# CM0_Controller_STM32F030C6T6.net
KiCad netlist of a schematic drawn in Altium Designer
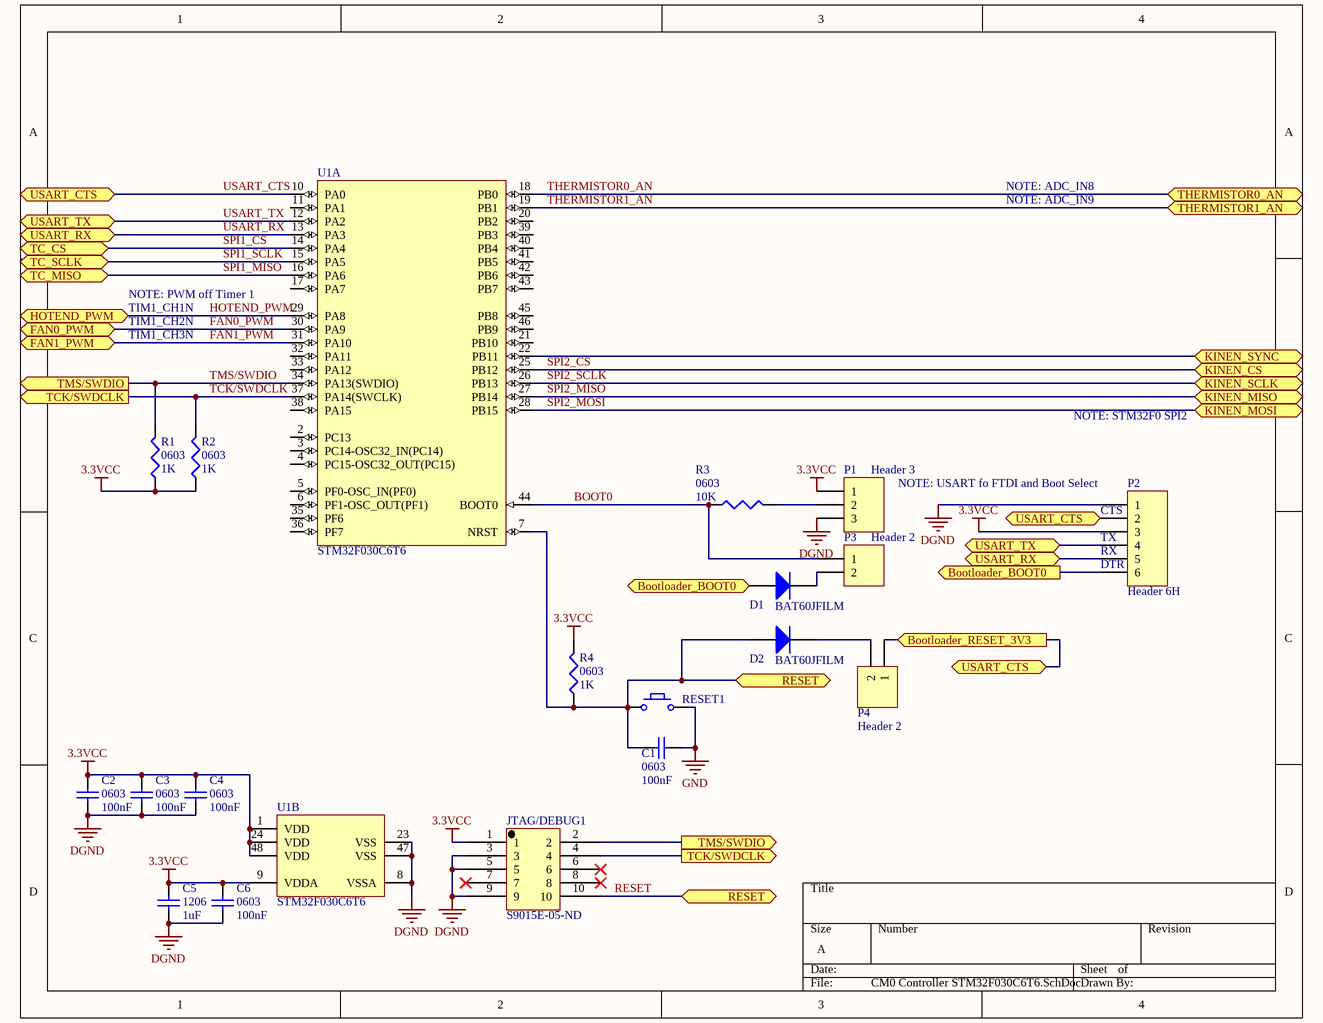
[diagram p0: CM0 Controller STM32F030C6T6.SchDoc]

(export (version "E")
  (design (tool "Eeschema 10.0.6"))
  (components
    (comp (ref "C1")
      (value "0603")
      (footprint "1608[0603]")
      (description "Capacitor (Semiconductor SIM Model)")
      (fields (field (name "ALTIUM_VALUE") "100nF") (field (name "PUBLISHER") "Altium Limited"))
      (libsource (lib "Miscellaneous Devices") (part "Cap Semi"))
    )
    (comp (ref "C2")
      (value "0603")
      (footprint "1608[0603]")
      (description "Capacitor (Semiconductor SIM Model)")
      (fields (field (name "ALTIUM_VALUE") "100nF") (field (name "PUBLISHER") "Altium Limited"))
      (libsource (lib "Miscellaneous Devices") (part "Cap Semi"))
    )
    (comp (ref "C3")
      (value "0603")
      (footprint "1608[0603]")
      (description "Capacitor (Semiconductor SIM Model)")
      (fields (field (name "ALTIUM_VALUE") "100nF") (field (name "PUBLISHER") "Altium Limited"))
      (libsource (lib "Miscellaneous Devices") (part "Cap Semi"))
    )
    (comp (ref "C4")
      (value "0603")
      (footprint "1608[0603]")
      (description "Capacitor (Semiconductor SIM Model)")
      (fields (field (name "ALTIUM_VALUE") "100nF") (field (name "PUBLISHER") "Altium Limited"))
      (libsource (lib "Miscellaneous Devices") (part "Cap Semi"))
    )
    (comp (ref "C5")
      (value "1206")
      (footprint "C1206")
      (description "Capacitor (Semiconductor SIM Model)")
      (fields (field (name "ALTIUM_VALUE") "1uF") (field (name "PUBLISHER") "Altium Limited"))
      (libsource (lib "Miscellaneous Devices") (part "Cap Semi"))
    )
    (comp (ref "C6")
      (value "0603")
      (footprint "1608[0603]")
      (description "Capacitor (Semiconductor SIM Model)")
      (fields (field (name "ALTIUM_VALUE") "100nF") (field (name "PUBLISHER") "Altium Limited"))
      (libsource (lib "Miscellaneous Devices") (part "Cap Semi"))
    )
    (comp (ref "D1")
      (value "BAT60JFILM")
      (footprint "SOD-323")
      (description "Default Diode")
      (fields (field (name "PUBLISHER") "Altium Limited"))
      (libsource (lib "Miscellaneous Devices") (part "Diode"))
    )
    (comp (ref "D2")
      (value "BAT60JFILM")
      (footprint "SOD-323")
      (description "Default Diode")
      (fields (field (name "PUBLISHER") "Altium Limited"))
      (libsource (lib "Miscellaneous Devices") (part "Diode"))
    )
    (comp (ref "JTAG/DEBUG1")
      (value "S9015E-05-ND")
      (footprint "S9015E-05-ND")
      (libsource (lib "Adams Altium Library") (part "S9015E-05-ND"))
    )
    (comp (ref "P1")
      (value "Header 3")
      (footprint "HDR1X3")
      (description "Header, 3-Pin")
      (fields (field (name "PUBLISHER") "Altium Limited"))
      (libsource (lib "Miscellaneous Connectors") (part "Header 3"))
    )
    (comp (ref "P2")
      (value "Header 6H")
      (footprint "HDR1X6H")
      (description "Header, 6-Pin, Right Angle")
      (fields (field (name "PUBLISHER") "Altium Limited"))
      (libsource (lib "Miscellaneous Connectors") (part "Header 6H"))
    )
    (comp (ref "P3")
      (value "Header 2")
      (footprint "HDR1X2")
      (description "Header, 2-Pin")
      (fields (field (name "PUBLISHER") "Altium Limited"))
      (libsource (lib "Miscellaneous Connectors") (part "Header 2"))
    )
    (comp (ref "P4")
      (value "Header 2")
      (footprint "HDR1X2")
      (description "Header, 2-Pin")
      (fields (field (name "PUBLISHER") "Altium Limited"))
      (libsource (lib "") (part "Header 2_1"))
    )
    (comp (ref "R1")
      (value "0603")
      (footprint "J1-0603")
      (description "Resistor")
      (fields (field (name "ALTIUM_VALUE") "1K") (field (name "PUBLISHER") "Altium Limited"))
      (libsource (lib "Miscellaneous Devices") (part "Res3"))
    )
    (comp (ref "R2")
      (value "0603")
      (footprint "J1-0603")
      (description "Resistor")
      (fields (field (name "ALTIUM_VALUE") "1K") (field (name "PUBLISHER") "Altium Limited"))
      (libsource (lib "Miscellaneous Devices") (part "Res3"))
    )
    (comp (ref "R3")
      (value "0603")
      (footprint "J1-0603")
      (description "Resistor")
      (fields (field (name "ALTIUM_VALUE") "10K") (field (name "PUBLISHER") "Altium Limited"))
      (libsource (lib "Miscellaneous Devices") (part "Res3"))
    )
    (comp (ref "R4")
      (value "0603")
      (footprint "J1-0603")
      (description "Resistor")
      (fields (field (name "ALTIUM_VALUE") "1K") (field (name "PUBLISHER") "Altium Limited"))
      (libsource (lib "Miscellaneous Devices") (part "Res3"))
    )
    (comp (ref "RESET1")
      (value "Tactile Switch")
      (footprint "tactile switch")
      (libsource (lib "Adams Altium Library") (part "Tactile Switch"))
    )
    (comp (ref "U1")
      (value "STM32F030C6T6")
      (footprint "STM-LQFP48_L")
      (libsource (lib "STMicroelectronics STM32 F0") (part "STM32F030C6T6"))
    )
  )
  (nets
    (net (code "1") (name "/BOOT0") (class "Default")
      (node (ref "P3") (pin "1") (pinfunction "1_1") (pintype "passive"))
      (node (ref "R3") (pin "1") (pinfunction "1_1") (pintype "passive"))
      (node (ref "U1") (pin "44") (pinfunction "BOOT0_44") (pintype "input"))
    )
    (net (code "2") (name "/Bootloader_BOOT0") (class "Default")
      (node (ref "D1") (pin "1") (pinfunction "A_1") (pintype "passive"))
      (node (ref "P2") (pin "6") (pinfunction "6_6") (pintype "passive"))
    )
    (net (code "3") (name "/FAN0_PWM") (class "Default")
      (node (ref "U1") (pin "30") (pinfunction "PA9_30") (pintype "bidirectional"))
    )
    (net (code "4") (name "/FAN1_PWM") (class "Default")
      (node (ref "U1") (pin "31") (pinfunction "PA10_31") (pintype "bidirectional"))
    )
    (net (code "5") (name "/HOTEND_PWM") (class "Default")
      (node (ref "U1") (pin "29") (pinfunction "PA8_29") (pintype "bidirectional"))
    )
    (net (code "6") (name "/KINEN_SYNC") (class "Default")
      (node (ref "U1") (pin "22") (pinfunction "PB11_22") (pintype "bidirectional"))
    )
    (net (code "7") (name "/RESET") (class "Default")
      (node (ref "C1") (pin "2") (pinfunction "2_2") (pintype "passive"))
      (node (ref "D2") (pin "1") (pinfunction "A_1") (pintype "passive"))
      (node (ref "JTAG/DEBUG1") (pin "10") (pinfunction "10_10") (pintype "passive"))
      (node (ref "R4") (pin "1") (pinfunction "1_1") (pintype "passive"))
      (node (ref "RESET1") (pin "1") (pintype "passive"))
      (node (ref "U1") (pin "7") (pinfunction "NRST_7") (pintype "bidirectional"))
    )
    (net (code "8") (name "/SPI1_CS") (class "Default")
      (node (ref "U1") (pin "14") (pinfunction "PA4_14") (pintype "bidirectional"))
    )
    (net (code "9") (name "/SPI1_MISO") (class "Default")
      (node (ref "U1") (pin "16") (pinfunction "PA6_16") (pintype "bidirectional"))
    )
    (net (code "10") (name "/SPI1_SCLK") (class "Default")
      (node (ref "U1") (pin "15") (pinfunction "PA5_15") (pintype "bidirectional"))
    )
    (net (code "11") (name "/SPI2_CS") (class "Default")
      (node (ref "U1") (pin "25") (pinfunction "PB12_25") (pintype "bidirectional"))
    )
    (net (code "12") (name "/SPI2_MISO") (class "Default")
      (node (ref "U1") (pin "27") (pinfunction "PB14_27") (pintype "bidirectional"))
    )
    (net (code "13") (name "/SPI2_MOSI") (class "Default")
      (node (ref "U1") (pin "28") (pinfunction "PB15_28") (pintype "bidirectional"))
    )
    (net (code "14") (name "/SPI2_SCLK") (class "Default")
      (node (ref "U1") (pin "26") (pinfunction "PB13_26") (pintype "bidirectional"))
    )
    (net (code "15") (name "/TCK{slash}SWDCLK") (class "Default")
      (node (ref "JTAG/DEBUG1") (pin "4") (pinfunction "4_4") (pintype "passive"))
      (node (ref "R2") (pin "2") (pinfunction "2_2") (pintype "passive"))
      (node (ref "U1") (pin "37") (pinfunction "PA14(SWCLK)_37") (pintype "bidirectional"))
    )
    (net (code "16") (name "/THERMISTOR0_AN") (class "Default")
      (node (ref "U1") (pin "18") (pinfunction "PB0_18") (pintype "bidirectional"))
    )
    (net (code "17") (name "/THERMISTOR1_AN") (class "Default")
      (node (ref "U1") (pin "19") (pinfunction "PB1_19") (pintype "bidirectional"))
    )
    (net (code "18") (name "/TMS{slash}SWDIO") (class "Default")
      (node (ref "JTAG/DEBUG1") (pin "2") (pinfunction "2_2") (pintype "passive"))
      (node (ref "R1") (pin "2") (pinfunction "2_2") (pintype "passive"))
      (node (ref "U1") (pin "34") (pinfunction "PA13(SWDIO)_34") (pintype "bidirectional"))
    )
    (net (code "19") (name "/USART_CTS") (class "Default")
      (node (ref "P2") (pin "2") (pinfunction "2_2") (pintype "passive"))
      (node (ref "P4") (pin "1") (pinfunction "1_1") (pintype "passive"))
      (node (ref "U1") (pin "10") (pinfunction "PA0_10") (pintype "bidirectional"))
    )
    (net (code "20") (name "/USART_RX") (class "Default")
      (node (ref "P2") (pin "5") (pinfunction "5_5") (pintype "passive"))
      (node (ref "U1") (pin "13") (pinfunction "PA3_13") (pintype "bidirectional"))
    )
    (net (code "21") (name "/USART_TX") (class "Default")
      (node (ref "P2") (pin "4") (pinfunction "4_4") (pintype "passive"))
      (node (ref "U1") (pin "12") (pinfunction "PA2_12") (pintype "bidirectional"))
    )
    (net (code "22") (name "3.3VCC") (class "Default")
      (node (ref "C2") (pin "2") (pinfunction "2_2") (pintype "passive"))
      (node (ref "C3") (pin "2") (pinfunction "2_2") (pintype "passive"))
      (node (ref "C4") (pin "2") (pinfunction "2_2") (pintype "passive"))
      (node (ref "C5") (pin "1") (pinfunction "1_1") (pintype "passive"))
      (node (ref "C6") (pin "1") (pinfunction "1_1") (pintype "passive"))
      (node (ref "JTAG/DEBUG1") (pin "1") (pinfunction "1_1") (pintype "passive"))
      (node (ref "P1") (pin "1") (pinfunction "1_1") (pintype "passive"))
      (node (ref "P2") (pin "3") (pinfunction "3_3") (pintype "passive"))
      (node (ref "R1") (pin "1") (pinfunction "1_1") (pintype "passive"))
      (node (ref "R2") (pin "1") (pinfunction "1_1") (pintype "passive"))
      (node (ref "R4") (pin "2") (pinfunction "2_2") (pintype "passive"))
      (node (ref "U1") (pin "1") (pinfunction "VDD_1") (pintype "power_in"))
      (node (ref "U1") (pin "24") (pinfunction "VDD_24") (pintype "power_in"))
      (node (ref "U1") (pin "48") (pinfunction "VDD_48") (pintype "power_in"))
      (node (ref "U1") (pin "9") (pinfunction "VDDA_9") (pintype "power_in"))
    )
    (net (code "23") (name "DGND") (class "Default")
      (node (ref "C2") (pin "1") (pinfunction "1_1") (pintype "passive"))
      (node (ref "C3") (pin "1") (pinfunction "1_1") (pintype "passive"))
      (node (ref "C4") (pin "1") (pinfunction "1_1") (pintype "passive"))
      (node (ref "C5") (pin "2") (pinfunction "2_2") (pintype "passive"))
      (node (ref "C6") (pin "2") (pinfunction "2_2") (pintype "passive"))
      (node (ref "JTAG/DEBUG1") (pin "3") (pinfunction "3_3") (pintype "passive"))
      (node (ref "JTAG/DEBUG1") (pin "5") (pinfunction "5_5") (pintype "passive"))
      (node (ref "JTAG/DEBUG1") (pin "9") (pinfunction "9_9") (pintype "passive"))
      (node (ref "P1") (pin "3") (pinfunction "3_3") (pintype "passive"))
      (node (ref "P2") (pin "1") (pinfunction "1_1") (pintype "passive"))
      (node (ref "U1") (pin "23") (pinfunction "VSS_23") (pintype "power_in"))
      (node (ref "U1") (pin "47") (pinfunction "VSS_47") (pintype "power_in"))
      (node (ref "U1") (pin "8") (pinfunction "VSSA_8") (pintype "power_in"))
    )
    (net (code "24") (name "GND") (class "Default")
      (node (ref "C1") (pin "1") (pinfunction "1_1") (pintype "passive"))
      (node (ref "RESET1") (pin "2") (pintype "passive"))
    )
    (net (code "25") (name "Net-(D1-K)") (class "Default")
      (node (ref "D1") (pin "2") (pinfunction "K_2") (pintype "passive"))
      (node (ref "P3") (pin "2") (pinfunction "2_2") (pintype "passive"))
    )
    (net (code "26") (name "Net-(D2-K)") (class "Default")
      (node (ref "D2") (pin "2") (pinfunction "K_2") (pintype "passive"))
      (node (ref "P4") (pin "2") (pinfunction "2_2") (pintype "passive"))
    )
    (net (code "27") (name "Net-(P1-Pad2)") (class "Default")
      (node (ref "P1") (pin "2") (pinfunction "2_2") (pintype "passive"))
      (node (ref "R3") (pin "2") (pinfunction "2_2") (pintype "passive"))
    )
    (net (code "28") (name "unconnected-(JTAG/DEBUG1-Pad6)") (class "Default")
      (node (ref "JTAG/DEBUG1") (pin "6") (pinfunction "6_6") (pintype "passive+no_connect"))
    )
    (net (code "29") (name "unconnected-(JTAG/DEBUG1-Pad7)") (class "Default")
      (node (ref "JTAG/DEBUG1") (pin "7") (pinfunction "7_7") (pintype "passive+no_connect"))
    )
    (net (code "30") (name "unconnected-(JTAG/DEBUG1-Pad8)") (class "Default")
      (node (ref "JTAG/DEBUG1") (pin "8") (pinfunction "8_8") (pintype "passive+no_connect"))
    )
    (net (code "31") (name "unconnected-(U1A-PA1-Pad11)") (class "Default")
      (node (ref "U1") (pin "11") (pinfunction "PA1_11") (pintype "bidirectional"))
    )
    (net (code "32") (name "unconnected-(U1A-PA7-Pad17)") (class "Default")
      (node (ref "U1") (pin "17") (pinfunction "PA7_17") (pintype "bidirectional"))
    )
    (net (code "33") (name "unconnected-(U1A-PA11-Pad32)") (class "Default")
      (node (ref "U1") (pin "32") (pinfunction "PA11_32") (pintype "bidirectional"))
    )
    (net (code "34") (name "unconnected-(U1A-PA12-Pad33)") (class "Default")
      (node (ref "U1") (pin "33") (pinfunction "PA12_33") (pintype "bidirectional"))
    )
    (net (code "35") (name "unconnected-(U1A-PA15-Pad38)") (class "Default")
      (node (ref "U1") (pin "38") (pinfunction "PA15_38") (pintype "bidirectional"))
    )
    (net (code "36") (name "unconnected-(U1A-PB2-Pad20)") (class "Default")
      (node (ref "U1") (pin "20") (pinfunction "PB2_20") (pintype "bidirectional"))
    )
    (net (code "37") (name "unconnected-(U1A-PB3-Pad39)") (class "Default")
      (node (ref "U1") (pin "39") (pinfunction "PB3_39") (pintype "bidirectional"))
    )
    (net (code "38") (name "unconnected-(U1A-PB4-Pad40)") (class "Default")
      (node (ref "U1") (pin "40") (pinfunction "PB4_40") (pintype "bidirectional"))
    )
    (net (code "39") (name "unconnected-(U1A-PB5-Pad41)") (class "Default")
      (node (ref "U1") (pin "41") (pinfunction "PB5_41") (pintype "bidirectional"))
    )
    (net (code "40") (name "unconnected-(U1A-PB6-Pad42)") (class "Default")
      (node (ref "U1") (pin "42") (pinfunction "PB6_42") (pintype "bidirectional"))
    )
    (net (code "41") (name "unconnected-(U1A-PB7-Pad43)") (class "Default")
      (node (ref "U1") (pin "43") (pinfunction "PB7_43") (pintype "bidirectional"))
    )
    (net (code "42") (name "unconnected-(U1A-PB8-Pad45)") (class "Default")
      (node (ref "U1") (pin "45") (pinfunction "PB8_45") (pintype "bidirectional"))
    )
    (net (code "43") (name "unconnected-(U1A-PB9-Pad46)") (class "Default")
      (node (ref "U1") (pin "46") (pinfunction "PB9_46") (pintype "bidirectional"))
    )
    (net (code "44") (name "unconnected-(U1A-PB10-Pad21)") (class "Default")
      (node (ref "U1") (pin "21") (pinfunction "PB10_21") (pintype "bidirectional"))
    )
    (net (code "45") (name "unconnected-(U1A-PC13-Pad2)") (class "Default")
      (node (ref "U1") (pin "2") (pinfunction "PC13_2") (pintype "bidirectional"))
    )
    (net (code "46") (name "unconnected-(U1A-PC14-OSC32_IN(PC14)-Pad3)") (class "Default")
      (node (ref "U1") (pin "3") (pinfunction "PC14-OSC32_IN(PC14)_3") (pintype "bidirectional"))
    )
    (net (code "47") (name "unconnected-(U1A-PC15-OSC32_OUT(PC15)-Pad4)") (class "Default")
      (node (ref "U1") (pin "4") (pinfunction "PC15-OSC32_OUT(PC15)_4") (pintype "bidirectional"))
    )
    (net (code "48") (name "unconnected-(U1A-PF0-OSC_IN(PF0)-Pad5)") (class "Default")
      (node (ref "U1") (pin "5") (pinfunction "PF0-OSC_IN(PF0)_5") (pintype "bidirectional"))
    )
    (net (code "49") (name "unconnected-(U1A-PF1-OSC_OUT(PF1)-Pad6)") (class "Default")
      (node (ref "U1") (pin "6") (pinfunction "PF1-OSC_OUT(PF1)_6") (pintype "bidirectional"))
    )
    (net (code "50") (name "unconnected-(U1A-PF6-Pad35)") (class "Default")
      (node (ref "U1") (pin "35") (pinfunction "PF6_35") (pintype "bidirectional"))
    )
    (net (code "51") (name "unconnected-(U1A-PF7-Pad36)") (class "Default")
      (node (ref "U1") (pin "36") (pinfunction "PF7_36") (pintype "bidirectional"))
    )
  )
)
